# GTM_PowerCircuits.net
KiCad netlist of a schematic drawn in Altium Designer
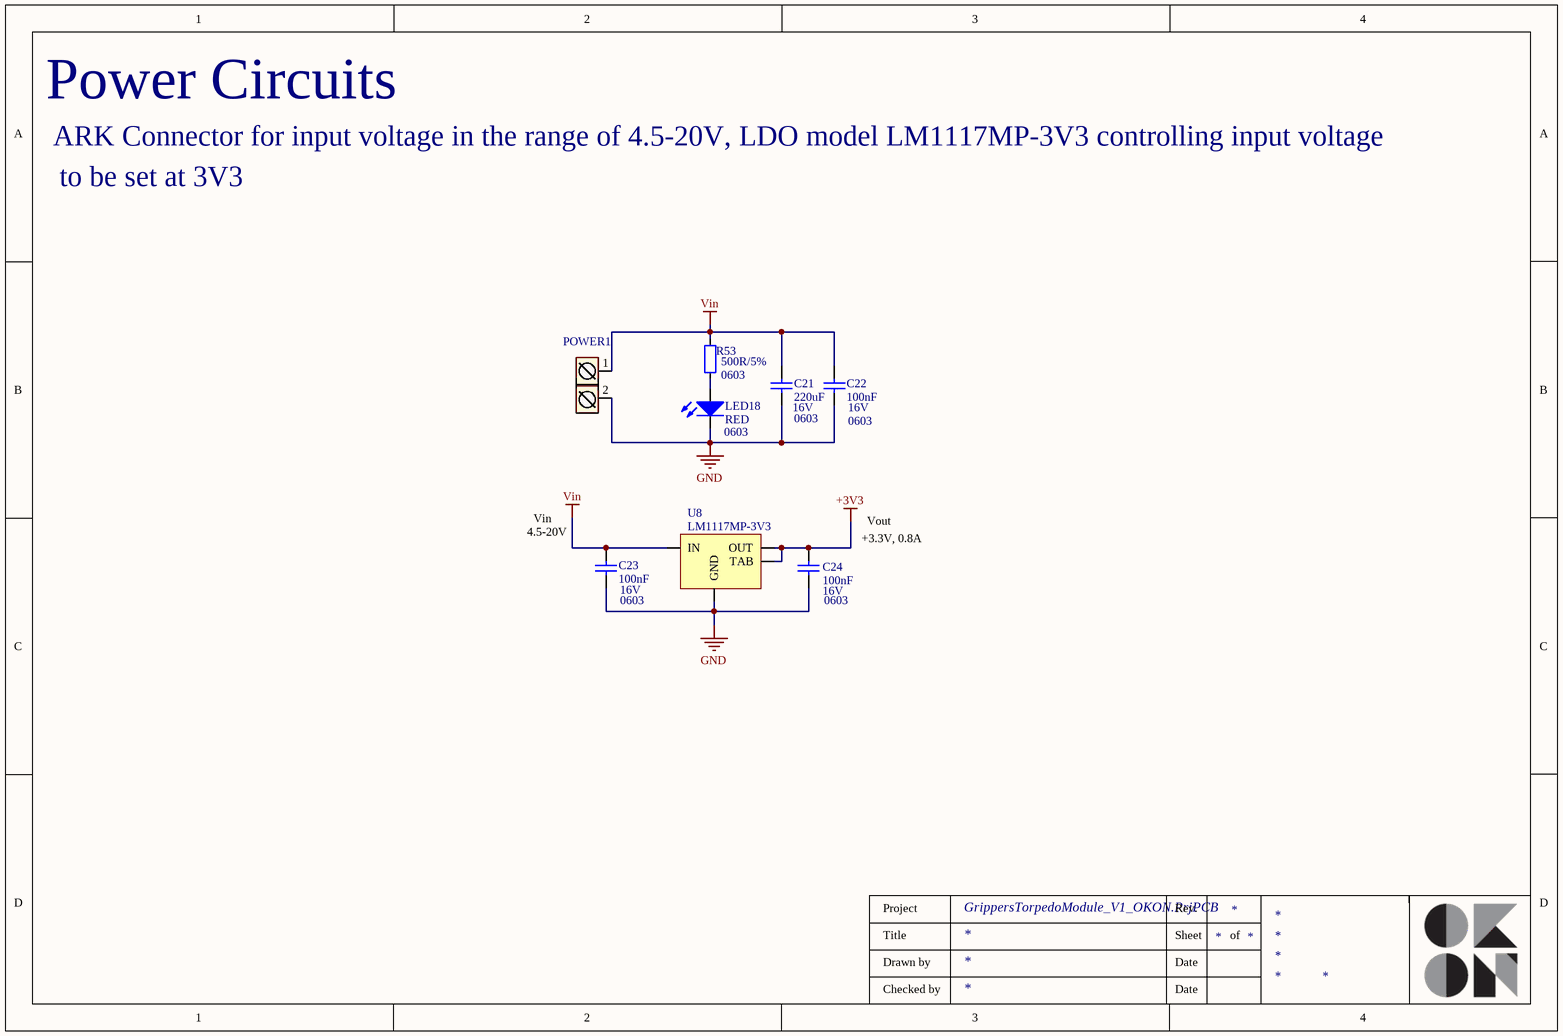
[diagram p0: GTM_PowerCircuits.SchDoc]

(export (version "E")
  (design (tool "Eeschema 10.0.6"))
  (components
    (comp (ref "C21")
      (value "220uF")
      (footprint "0603_CAP")
      (description "Ceramic capacitor")
      (fields (field (name "PACKAGE") "0603") (field (name "CAPACITY") "16V") (field (name "Comment") "Cap"))
      (libsource (lib "Library_Altium_KNR") (part "Cap"))
    )
    (comp (ref "C22")
      (value "100nF")
      (footprint "0603_CAP")
      (description "Ceramic capacitor")
      (fields (field (name "PACKAGE") "0603") (field (name "CAPACITY") "16V") (field (name "Comment") "Cap"))
      (libsource (lib "Library_Altium_KNR") (part "Cap"))
    )
    (comp (ref "C23")
      (value "100nF")
      (footprint "0603_CAP")
      (description "Ceramic capacitor")
      (fields (field (name "PACKAGE") "0603") (field (name "CAPACITY") "16V") (field (name "Comment") "Cap"))
      (libsource (lib "Library_Altium_KNR") (part "Cap"))
    )
    (comp (ref "C24")
      (value "100nF")
      (footprint "0603_CAP")
      (description "Ceramic capacitor")
      (fields (field (name "PACKAGE") "0603") (field (name "CAPACITY") "16V") (field (name "Comment") "Cap"))
      (libsource (lib "Library_Altium_KNR") (part "Cap"))
    )
    (comp (ref "LED18")
      (value "RED")
      (footprint "0603_led_red")
      (description "Light-emitting diode")
      (fields (field (name "PACKAGE") "0603"))
      (libsource (lib "KNR_Kurs") (part "LED"))
    )
    (comp (ref "POWER1")
      (value "ARK2")
      (footprint "ARK2")
      (description "Złącze śrubowe 2 piny")
      (libsource (lib "KNR_Kurs") (part "ARK2"))
    )
    (comp (ref "R53")
      (value "500R/5%")
      (footprint "0603")
      (description "Resistior")
      (fields (field (name "PACKAGE") "0603"))
      (libsource (lib "Library_Altium_KNR") (part "RES"))
    )
    (comp (ref "U8")
      (value "LM1117MP-3V3")
      (footprint "SOT223")
      (description "800mA Low-Dropout Linear Regulator")
      (fields
        (field (name "PARTNUMBER") "LM1117MP-3.3")
        (field (name "MANUFACTURER") "National Semiconductor")
        (field (name "PUBLISHER") "Altium Limited")
      )
      (libsource (lib "KNR_Kurs_K") (part "LM1117MP-3V3"))
    )
  )
  (nets
    (net (code "1") (name "+3V3") (class "Default")
      (node (ref "C24") (pin "1") (pinfunction "1_1") (pintype "passive"))
      (node (ref "U8") (pin "2") (pinfunction "OUT_2") (pintype "power_in"))
      (node (ref "U8") (pin "4") (pinfunction "TAB_4") (pintype "power_in"))
    )
    (net (code "2") (name "GND") (class "Default")
      (node (ref "C21") (pin "1") (pinfunction "1_1") (pintype "passive"))
      (node (ref "C22") (pin "1") (pinfunction "1_1") (pintype "passive"))
      (node (ref "C23") (pin "2") (pinfunction "2_2") (pintype "passive"))
      (node (ref "C24") (pin "2") (pinfunction "2_2") (pintype "passive"))
      (node (ref "LED18") (pin "2") (pinfunction "K_2") (pintype "passive"))
      (node (ref "POWER1") (pin "2") (pinfunction "2_2") (pintype "passive"))
      (node (ref "U8") (pin "1") (pinfunction "GND_1") (pintype "power_in"))
    )
    (net (code "3") (name "Net-(LED18-A)") (class "Default")
      (node (ref "LED18") (pin "1") (pinfunction "A_1") (pintype "passive"))
      (node (ref "R53") (pin "1") (pinfunction "1_1") (pintype "passive"))
    )
    (net (code "4") (name "Vin") (class "Default")
      (node (ref "C21") (pin "2") (pinfunction "2_2") (pintype "passive"))
      (node (ref "C22") (pin "2") (pinfunction "2_2") (pintype "passive"))
      (node (ref "C23") (pin "1") (pinfunction "1_1") (pintype "passive"))
      (node (ref "POWER1") (pin "1") (pinfunction "1_1") (pintype "passive"))
      (node (ref "R53") (pin "2") (pinfunction "2_2") (pintype "passive"))
      (node (ref "U8") (pin "3") (pinfunction "IN_3") (pintype "power_in"))
    )
  )
)
